# USB_Downstream_Type_C_Port_1.net
KiCad netlist of a schematic drawn in Altium Designer
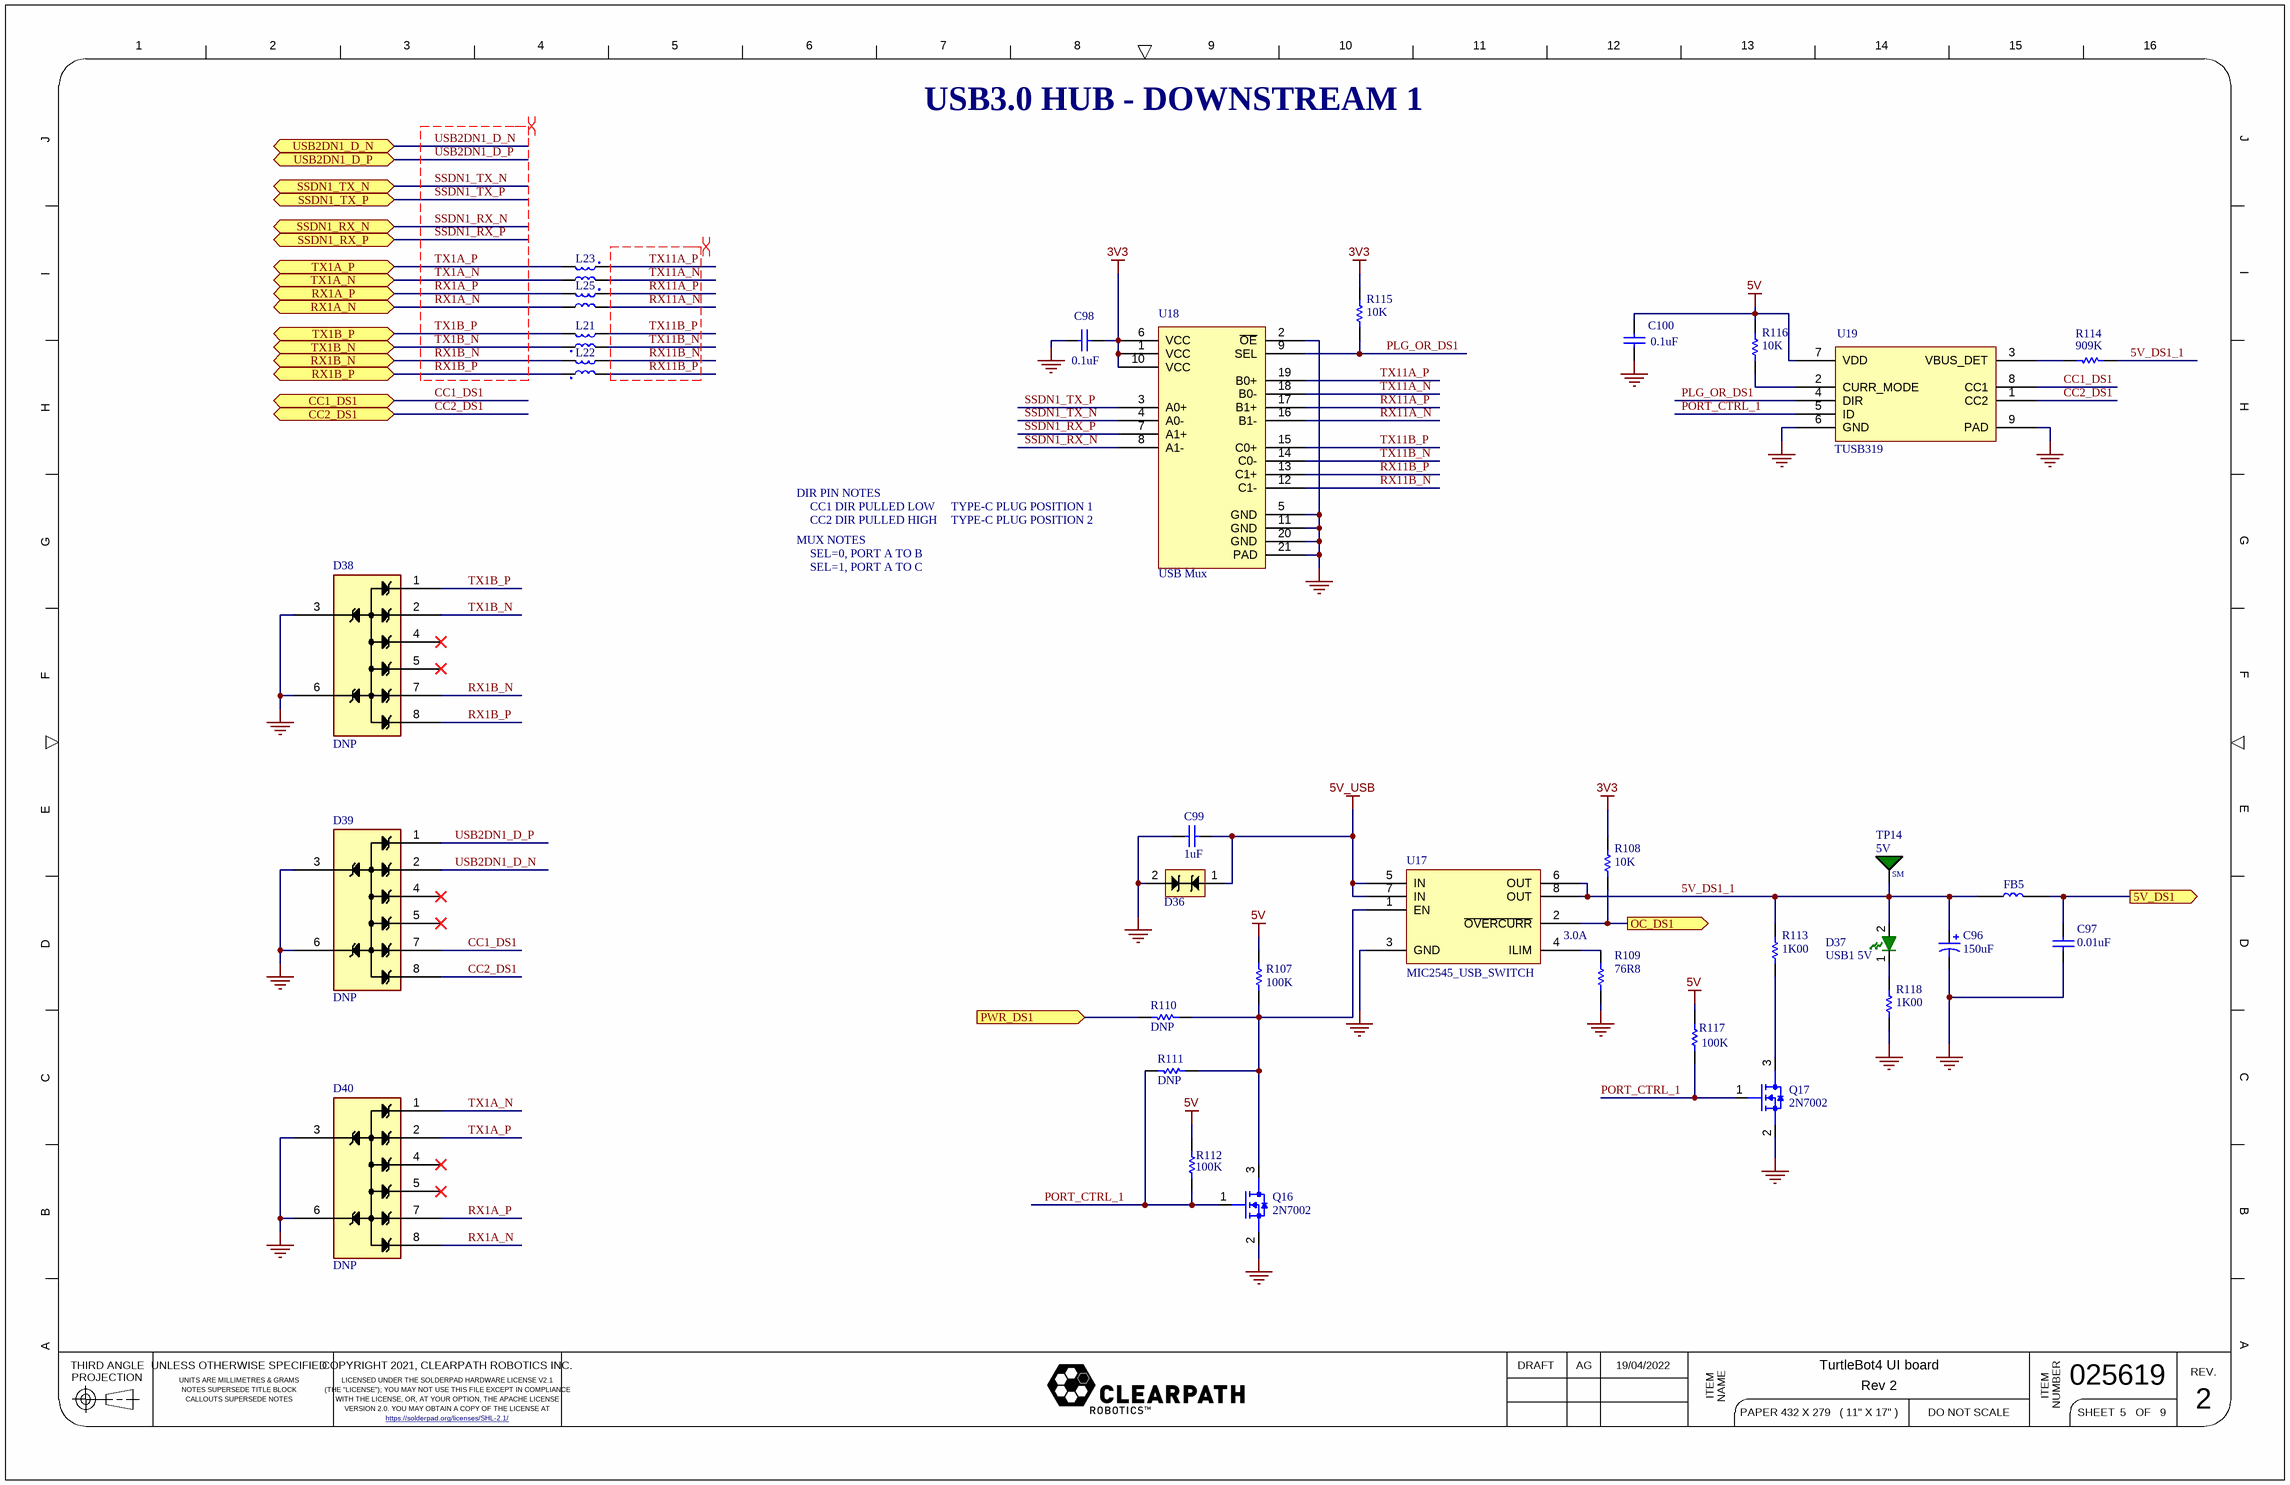
[diagram p0: USB Downstream Type C Port 1.SchDoc]

(export (version "E")
  (design (tool "Eeschema 10.0.6"))
  (components
    (comp (ref "C96")
      (value "150uF")
      (footprint "T494D157K016AT:CAPMP7.6X4.3_3.1N_KEM-M")
      (description "CAP TANT 150UF 10% 16V 2917")
      (fields (field (name "VOLTAGE") "16V") (field (name "TOLERANCE") "10%"))
      (libsource (lib "Miscellaneous Devices") (part "Cap Pol1"))
    )
    (comp (ref "C97")
      (value "0.01uF")
      (footprint "C0805")
      (description "Capacitor")
      (fields (field (name "TOLERANCE") "10%") (field (name "VOLTAGE") "50V"))
      (libsource (lib "CPR_CommonDevices") (part "Capacitor _SMT"))
    )
    (comp (ref "C98")
      (value "0.1uF")
      (footprint "C0805")
      (description "Capacitor")
      (fields (field (name "TOLERANCE") "10%") (field (name "VOLTAGE") "50V"))
      (libsource (lib "CPR_CommonDevices") (part "Capacitor _SMT"))
    )
    (comp (ref "C99")
      (value "1uF")
      (footprint "C0805")
      (description "Capacitor")
      (fields (field (name "TOLERANCE") "-20 +80") (field (name "VOLTAGE") "50V"))
      (libsource (lib "CPR_CommonDevices") (part "Capacitor _SMT"))
    )
    (comp (ref "C100")
      (value "0.1uF")
      (footprint "C0805")
      (description "Capacitor")
      (fields (field (name "TOLERANCE") "10%") (field (name "VOLTAGE") "50V"))
      (libsource (lib "CPR_CommonDevices") (part "Capacitor _SMT"))
    )
    (comp (ref "D36")
      (value "TVS DIODE BIDIR 15V SMC")
      (footprint "General PCB Library:DO-214AA")
      (description "TVS 600W 15V BI-DIR DO-214AA")
      (fields (field (name "MFG") "Littelfuse Inc."))
      (libsource (lib "SMBJ15CA") (part "TVS DIODE BIDIR 15V SMC"))
    )
    (comp (ref "D37")
      (value "USB1 5V")
      (footprint "LED_0805_GRN")
      (description "Green LED")
      (fields (field (name "MFG") "LiteOn"))
      (libsource (lib "Green LED") (part "GREEN_LED"))
    )
    (comp (ref "D38")
      (value "DNP")
      (footprint "ESD7016")
      (description "USB3 TVS diode assy")
      (fields (field (name "MFG") "ON Semi"))
      (libsource (lib "ONSemi_ESD7016") (part "ESD7016"))
    )
    (comp (ref "D39")
      (value "DNP")
      (footprint "ESD7016")
      (description "USB3 TVS diode assy")
      (fields (field (name "MFG") "ON Semi"))
      (libsource (lib "ONSemi_ESD7016") (part "ESD7016"))
    )
    (comp (ref "D40")
      (value "DNP")
      (footprint "ESD7016")
      (description "USB3 TVS diode assy")
      (fields (field (name "MFG") "ON Semi"))
      (libsource (lib "ONSemi_ESD7016") (part "ESD7016"))
    )
    (comp (ref "FB5")
      (value "742792602")
      (footprint "General PCB Library:R0603")
      (description "60 Ohms 1 Signal Line Ferrite Bead 0603 (1608 Metric) 3A 40mOhm")
      (libsource (lib "742792602") (part "742792602"))
    )
    (comp (ref "L21")
      (value "CMC 100MA 2LN 90 OHM SMD2")
      (footprint "cmc_90_ohms:cmc_90_ohms")
      (description "Line Common Mode Choke Surface Mount 90 Ohms 100mA DCR 5Ohm")
      (libsource (lib "cmc_90_ohms") (part "CMC 90_Ohms"))
    )
    (comp (ref "L22")
      (value "CMC 100MA 2LN 90 OHM SMD2")
      (footprint "cmc_90_ohms:cmc_90_ohms")
      (description "Line Common Mode Choke Surface Mount 90 Ohms 100mA DCR 5Ohm")
      (libsource (lib "cmc_90_ohms") (part "CMC 90_Ohms"))
    )
    (comp (ref "L23")
      (value "CMC 100MA 2LN 90 OHM SMD2")
      (footprint "cmc_90_ohms:cmc_90_ohms")
      (description "Line Common Mode Choke Surface Mount 90 Ohms 100mA DCR 5Ohm")
      (libsource (lib "cmc_90_ohms") (part "CMC 90_Ohms"))
    )
    (comp (ref "L25")
      (value "CMC 100MA 2LN 90 OHM SMD2")
      (footprint "cmc_90_ohms:cmc_90_ohms")
      (description "Line Common Mode Choke Surface Mount 90 Ohms 100mA DCR 5Ohm")
      (libsource (lib "cmc_90_ohms") (part "CMC 90_Ohms"))
    )
    (comp (ref "Q16")
      (value "NFET")
      (footprint "SOT-23-3")
      (fields (field (name "MFG PN") "2N7002") (field (name "MFG") "ON Semi"))
      (libsource (lib "NFET_SINGLE") (part "NFET_SNGL"))
    )
    (comp (ref "Q17")
      (value "NFET")
      (footprint "SOT-23-3")
      (fields (field (name "MFG PN") "2N7002") (field (name "MFG") "ON Semi"))
      (libsource (lib "NFET_SINGLE") (part "NFET_SNGL"))
    )
    (comp (ref "R107")
      (value "100K")
      (footprint "R0805")
      (description "Resistor")
      (fields (field (name "TOLERANCE") "1%") (field (name "MFG") "Yageo"))
      (libsource (lib "CPR_CommonDevices") (part "Resistor_SMT"))
    )
    (comp (ref "R108")
      (value "10K")
      (footprint "R0805")
      (description "Resistor")
      (fields (field (name "TOLERANCE") "1%") (field (name "MFG") "Yageo"))
      (libsource (lib "CPR_CommonDevices") (part "Resistor_SMT"))
    )
    (comp (ref "R109")
      (value "3.0A")
      (footprint "R0805")
      (description "Resistor")
      (fields
        (field (name "ALTIUM_VALUE") "76R8")
        (field (name "TOLERANCE") "1%")
        (field (name "MFG") "Yageo")
      )
      (libsource (lib "CPR_CommonDevices") (part "Resistor_SMT"))
    )
    (comp (ref "R110")
      (value "DNP")
      (footprint "R0805")
      (description "Resistor")
      (fields (field (name "MFG") "Yageo") (field (name "Comment") "Resistor_SMT"))
      (libsource (lib "") (part "Resistor_SMT_1"))
    )
    (comp (ref "R111")
      (value "DNP")
      (footprint "R0805")
      (description "Resistor")
      (fields (field (name "MFG") "Yageo") (field (name "Comment") "Resistor_SMT"))
      (libsource (lib "") (part "Resistor_SMT_1"))
    )
    (comp (ref "R112")
      (value "100K")
      (footprint "R0805")
      (description "Resistor")
      (fields (field (name "TOLERANCE") "1%") (field (name "MFG") "Yageo"))
      (libsource (lib "CPR_CommonDevices") (part "Resistor_SMT"))
    )
    (comp (ref "R113")
      (value "1K00")
      (footprint "R0805")
      (description "Resistor")
      (fields (field (name "TOLERANCE") "1%") (field (name "MFG") "Yageo"))
      (libsource (lib "CPR_CommonDevices") (part "Resistor_SMT"))
    )
    (comp (ref "R114")
      (value "909K")
      (footprint "R0805")
      (description "Resistor")
      (fields (field (name "TOLERANCE") "1%") (field (name "MFG") "Yageo"))
      (libsource (lib "CPR_CommonDevices") (part "Resistor_SMT"))
    )
    (comp (ref "R115")
      (value "10K")
      (footprint "R0805")
      (description "Resistor")
      (fields (field (name "TOLERANCE") "1%") (field (name "MFG") "Yageo"))
      (libsource (lib "CPR_CommonDevices") (part "Resistor_SMT"))
    )
    (comp (ref "R116")
      (value "10K")
      (footprint "R0805")
      (description "Resistor")
      (fields (field (name "TOLERANCE") "1%") (field (name "MFG") "Yageo"))
      (libsource (lib "CPR_CommonDevices") (part "Resistor_SMT"))
    )
    (comp (ref "R117")
      (value "100K")
      (footprint "R0805")
      (description "Resistor")
      (fields (field (name "TOLERANCE") "1%") (field (name "MFG") "Yageo"))
      (libsource (lib "CPR_CommonDevices") (part "Resistor_SMT"))
    )
    (comp (ref "R118")
      (value "1K00")
      (footprint "R0805")
      (description "Resistor")
      (fields (field (name "TOLERANCE") "1%") (field (name "MFG") "Yageo"))
      (libsource (lib "CPR_CommonDevices") (part "Resistor_SMT"))
    )
    (comp (ref "TP14")
      (value "5V")
      (footprint "TP_28SM")
      (description "Test point, 28 Mil exposed pad")
      (fields (field (name "MANUFACTURER") "Clearpath Robotics Inc."))
      (libsource (lib "Test Points") (part "TP_28SM"))
    )
    (comp (ref "U17")
      (value "MIC2545_USB_SWITCH")
      (footprint "SOIC-8-150")
      (description "IC PWR SWITCH N-CHAN 1:1 8SOIC")
      (fields (field (name "MFG") "Microchip"))
      (libsource (lib "MIC2545") (part "MIC2545_USB_SWITCH"))
    )
    (comp (ref "U18")
      (value "USB Mux")
      (footprint "TQFN20")
      (description "TC7PCI3212MT,LF USB3.0 Mux")
      (fields (field (name "MANUFACTURER") "Toshiba"))
      (libsource (lib "TOSHIBA TC7PCI3212MT") (part "TC7PCI3212"))
    )
    (comp (ref "U19")
      (value "TUSB319")
      (footprint "WSON8")
      (description "USB Type C Controller")
      (fields (field (name "MFG") "Texas Instruments"))
      (libsource (lib "TUSB319") (part "TUSB319"))
    )
  )
  (nets
    (net (code "1") (name "/5V_DS1") (class "Default")
      (node (ref "C97") (pin "1") (pinfunction "1_1") (pintype "passive"))
      (node (ref "FB5") (pin "2") (pinfunction "2_2") (pintype "passive"))
    )
    (net (code "2") (name "/5V_DS1_1") (class "Default")
      (node (ref "C96") (pin "1") (pinfunction "1_1") (pintype "passive"))
      (node (ref "D37") (pin "2") (pinfunction "RA_2") (pintype "passive"))
      (node (ref "FB5") (pin "1") (pinfunction "1_1") (pintype "passive"))
      (node (ref "R113") (pin "1") (pinfunction "1_1") (pintype "passive"))
      (node (ref "R114") (pin "2") (pinfunction "2_2") (pintype "passive"))
      (node (ref "TP14") (pin "1") (pintype "passive"))
      (node (ref "U17") (pin "6") (pinfunction "OUT_6") (pintype "passive"))
      (node (ref "U17") (pin "8") (pinfunction "OUT_8") (pintype "passive"))
    )
    (net (code "3") (name "/CC1_DS1") (class "Default")
      (node (ref "D39") (pin "7") (pintype "passive"))
      (node (ref "U19") (pin "8") (pinfunction "CC1_8") (pintype "passive"))
    )
    (net (code "4") (name "/CC2_DS1") (class "Default")
      (node (ref "D39") (pin "8") (pintype "passive"))
      (node (ref "U19") (pin "1") (pinfunction "CC2_1") (pintype "passive"))
    )
    (net (code "5") (name "/OC_DS1") (class "Default")
      (node (ref "R108") (pin "2") (pinfunction "2_2") (pintype "passive"))
      (node (ref "U17") (pin "2") (pinfunction "~{OVERCURR}_2") (pintype "passive"))
    )
    (net (code "6") (name "/PLG_OR_DS1") (class "Default")
      (node (ref "R115") (pin "2") (pinfunction "2_2") (pintype "passive"))
      (node (ref "U18") (pin "9") (pinfunction "SEL_9") (pintype "passive"))
      (node (ref "U19") (pin "4") (pinfunction "DIR_4") (pintype "passive"))
    )
    (net (code "7") (name "/PORT_CTRL_1") (class "Default")
      (node (ref "Q16") (pin "1") (pinfunction "G1_1") (pintype "passive"))
      (node (ref "Q17") (pin "1") (pinfunction "G1_1") (pintype "passive"))
      (node (ref "R111") (pin "1") (pinfunction "1_1") (pintype "passive"))
      (node (ref "R112") (pin "1") (pinfunction "1_1") (pintype "passive"))
      (node (ref "R117") (pin "1") (pinfunction "1_1") (pintype "passive"))
      (node (ref "U19") (pin "5") (pinfunction "ID_5") (pintype "passive"))
    )
    (net (code "8") (name "/PWR_DS1") (class "Default")
      (node (ref "R110") (pin "1") (pinfunction "1_1") (pintype "passive"))
    )
    (net (code "9") (name "/RX1A_N") (class "Default")
      (node (ref "D40") (pin "8") (pintype "passive"))
      (node (ref "L25") (pin "3") (pinfunction "3_3") (pintype "passive"))
    )
    (net (code "10") (name "/RX1A_P") (class "Default")
      (node (ref "D40") (pin "7") (pintype "passive"))
      (node (ref "L25") (pin "4") (pinfunction "4_4") (pintype "passive"))
    )
    (net (code "11") (name "/RX1B_N") (class "Default")
      (node (ref "D38") (pin "7") (pintype "passive"))
      (node (ref "L22") (pin "2") (pinfunction "2_2") (pintype "passive"))
    )
    (net (code "12") (name "/RX1B_P") (class "Default")
      (node (ref "D38") (pin "8") (pintype "passive"))
      (node (ref "L22") (pin "1") (pinfunction "1_1") (pintype "passive"))
    )
    (net (code "13") (name "/RX11A_N") (class "Default")
      (node (ref "L25") (pin "2") (pinfunction "2_2") (pintype "passive"))
      (node (ref "U18") (pin "16") (pinfunction "B1-_16") (pintype "passive"))
    )
    (net (code "14") (name "/RX11A_P") (class "Default")
      (node (ref "L25") (pin "1") (pinfunction "1_1") (pintype "passive"))
      (node (ref "U18") (pin "17") (pinfunction "B1+_17") (pintype "passive"))
    )
    (net (code "15") (name "/RX11B_N") (class "Default")
      (node (ref "L22") (pin "3") (pinfunction "3_3") (pintype "passive"))
      (node (ref "U18") (pin "12") (pinfunction "C1-_12") (pintype "passive"))
    )
    (net (code "16") (name "/RX11B_P") (class "Default")
      (node (ref "L22") (pin "4") (pinfunction "4_4") (pintype "passive"))
      (node (ref "U18") (pin "13") (pinfunction "C1+_13") (pintype "passive"))
    )
    (net (code "17") (name "/SSDN1_RX_N") (class "Default")
      (node (ref "U18") (pin "8") (pinfunction "A1-_8") (pintype "passive"))
    )
    (net (code "18") (name "/SSDN1_RX_P") (class "Default")
      (node (ref "U18") (pin "7") (pinfunction "A1+_7") (pintype "passive"))
    )
    (net (code "19") (name "/SSDN1_TX_N") (class "Default")
      (node (ref "U18") (pin "4") (pinfunction "A0-_4") (pintype "passive"))
    )
    (net (code "20") (name "/SSDN1_TX_P") (class "Default")
      (node (ref "U18") (pin "3") (pinfunction "A0+_3") (pintype "passive"))
    )
    (net (code "21") (name "/TX1A_N") (class "Default")
      (node (ref "D40") (pin "1") (pinfunction "1_1") (pintype "passive"))
      (node (ref "L23") (pin "3") (pinfunction "3_3") (pintype "passive"))
    )
    (net (code "22") (name "/TX1A_P") (class "Default")
      (node (ref "D40") (pin "2") (pintype "passive"))
      (node (ref "L23") (pin "4") (pinfunction "4_4") (pintype "passive"))
    )
    (net (code "23") (name "/TX1B_N") (class "Default")
      (node (ref "D38") (pin "2") (pintype "passive"))
      (node (ref "L21") (pin "1") (pinfunction "1_1") (pintype "passive"))
    )
    (net (code "24") (name "/TX1B_P") (class "Default")
      (node (ref "D38") (pin "1") (pinfunction "1_1") (pintype "passive"))
      (node (ref "L21") (pin "2") (pinfunction "2_2") (pintype "passive"))
    )
    (net (code "25") (name "/TX11A_N") (class "Default")
      (node (ref "L23") (pin "2") (pinfunction "2_2") (pintype "passive"))
      (node (ref "U18") (pin "18") (pinfunction "B0-_18") (pintype "passive"))
    )
    (net (code "26") (name "/TX11A_P") (class "Default")
      (node (ref "L23") (pin "1") (pinfunction "1_1") (pintype "passive"))
      (node (ref "U18") (pin "19") (pinfunction "B0+_19") (pintype "passive"))
    )
    (net (code "27") (name "/TX11B_N") (class "Default")
      (node (ref "L21") (pin "4") (pinfunction "4_4") (pintype "passive"))
      (node (ref "U18") (pin "14") (pinfunction "C0-_14") (pintype "passive"))
    )
    (net (code "28") (name "/TX11B_P") (class "Default")
      (node (ref "L21") (pin "3") (pinfunction "3_3") (pintype "passive"))
      (node (ref "U18") (pin "15") (pinfunction "C0+_15") (pintype "passive"))
    )
    (net (code "29") (name "/USB2DN1_D_N") (class "Default") (node (ref "D39") (pin "2") (pintype "passive")))
    (net (code "30") (name "/USB2DN1_D_P") (class "Default")
      (node (ref "D39") (pin "1") (pinfunction "1_1") (pintype "passive"))
    )
    (net (code "31") (name "3V3") (class "Default")
      (node (ref "C98") (pin "1") (pinfunction "1_1") (pintype "passive"))
      (node (ref "R108") (pin "1") (pinfunction "1_1") (pintype "passive"))
      (node (ref "R115") (pin "1") (pinfunction "1_1") (pintype "passive"))
      (node (ref "U18") (pin "1") (pinfunction "VCC_1") (pintype "passive"))
      (node (ref "U18") (pin "10") (pinfunction "VCC_10") (pintype "passive"))
      (node (ref "U18") (pin "6") (pinfunction "VCC_6") (pintype "passive"))
    )
    (net (code "32") (name "5V") (class "Default")
      (node (ref "C100") (pin "1") (pinfunction "1_1") (pintype "passive"))
      (node (ref "R107") (pin "2") (pinfunction "2_2") (pintype "passive"))
      (node (ref "R112") (pin "2") (pinfunction "2_2") (pintype "passive"))
      (node (ref "R116") (pin "1") (pinfunction "1_1") (pintype "passive"))
      (node (ref "R117") (pin "2") (pinfunction "2_2") (pintype "passive"))
      (node (ref "U19") (pin "7") (pinfunction "VDD_7") (pintype "passive"))
    )
    (net (code "33") (name "5V_USB") (class "Default")
      (node (ref "C99") (pin "2") (pinfunction "2_2") (pintype "passive"))
      (node (ref "D36") (pin "1") (pintype "passive"))
      (node (ref "U17") (pin "5") (pinfunction "IN_5") (pintype "passive"))
      (node (ref "U17") (pin "7") (pinfunction "IN_7") (pintype "passive"))
    )
    (net (code "34") (name "GND") (class "Default")
      (node (ref "C100") (pin "2") (pinfunction "2_2") (pintype "passive"))
      (node (ref "C96") (pin "2") (pinfunction "2_2") (pintype "passive"))
      (node (ref "C97") (pin "2") (pinfunction "2_2") (pintype "passive"))
      (node (ref "C98") (pin "2") (pinfunction "2_2") (pintype "passive"))
      (node (ref "C99") (pin "1") (pinfunction "1_1") (pintype "passive"))
      (node (ref "D36") (pin "2") (pintype "passive"))
      (node (ref "D38") (pin "3") (pintype "passive"))
      (node (ref "D38") (pin "6") (pintype "passive"))
      (node (ref "D39") (pin "3") (pintype "passive"))
      (node (ref "D39") (pin "6") (pintype "passive"))
      (node (ref "D40") (pin "3") (pintype "passive"))
      (node (ref "D40") (pin "6") (pintype "passive"))
      (node (ref "Q16") (pin "2") (pinfunction "D1_2") (pintype "passive"))
      (node (ref "Q17") (pin "2") (pinfunction "D1_2") (pintype "passive"))
      (node (ref "R109") (pin "1") (pinfunction "1_1") (pintype "passive"))
      (node (ref "R118") (pin "2") (pinfunction "2_2") (pintype "passive"))
      (node (ref "U17") (pin "3") (pinfunction "GND_3") (pintype "passive"))
      (node (ref "U18") (pin "11") (pinfunction "GND_11") (pintype "passive"))
      (node (ref "U18") (pin "2") (pinfunction "~{OE}_2") (pintype "passive"))
      (node (ref "U18") (pin "20") (pinfunction "GND_20") (pintype "passive"))
      (node (ref "U18") (pin "21") (pinfunction "PAD_21") (pintype "passive"))
      (node (ref "U18") (pin "5") (pinfunction "GND_5") (pintype "passive"))
      (node (ref "U19") (pin "6") (pinfunction "GND_6") (pintype "passive"))
      (node (ref "U19") (pin "9") (pinfunction "PAD_9") (pintype "passive"))
    )
    (net (code "35") (name "Net-(D37-RK)") (class "Default")
      (node (ref "D37") (pin "1") (pinfunction "RK_1") (pintype "passive"))
      (node (ref "R118") (pin "1") (pinfunction "1_1") (pintype "passive"))
    )
    (net (code "36") (name "Net-(Q16-S1)") (class "Default")
      (node (ref "Q16") (pin "3") (pinfunction "S1_3") (pintype "passive"))
      (node (ref "R107") (pin "1") (pinfunction "1_1") (pintype "passive"))
      (node (ref "R110") (pin "2") (pinfunction "2_2") (pintype "passive"))
      (node (ref "R111") (pin "2") (pinfunction "2_2") (pintype "passive"))
      (node (ref "U17") (pin "1") (pinfunction "EN_1") (pintype "passive"))
    )
    (net (code "37") (name "Net-(Q17-S1)") (class "Default")
      (node (ref "Q17") (pin "3") (pinfunction "S1_3") (pintype "passive"))
      (node (ref "R113") (pin "2") (pinfunction "2_2") (pintype "passive"))
    )
    (net (code "38") (name "Net-(U17-ILIM)") (class "Default")
      (node (ref "R109") (pin "2") (pinfunction "2_2") (pintype "passive"))
      (node (ref "U17") (pin "4") (pinfunction "ILIM_4") (pintype "passive"))
    )
    (net (code "39") (name "Net-(U19-CURR_MODE)") (class "Default")
      (node (ref "R116") (pin "2") (pinfunction "2_2") (pintype "passive"))
      (node (ref "U19") (pin "2") (pinfunction "CURR_MODE_2") (pintype "passive"))
    )
    (net (code "40") (name "Net-(U19-VBUS_DET)") (class "Default")
      (node (ref "R114") (pin "1") (pinfunction "1_1") (pintype "passive"))
      (node (ref "U19") (pin "3") (pinfunction "VBUS_DET_3") (pintype "passive"))
    )
    (net (code "41") (name "unconnected-(D38-Pad4)") (class "Default")
      (node (ref "D38") (pin "4") (pintype "passive+no_connect"))
    )
    (net (code "42") (name "unconnected-(D38-Pad5)") (class "Default")
      (node (ref "D38") (pin "5") (pintype "passive+no_connect"))
    )
    (net (code "43") (name "unconnected-(D39-Pad4)") (class "Default")
      (node (ref "D39") (pin "4") (pintype "passive+no_connect"))
    )
    (net (code "44") (name "unconnected-(D39-Pad5)") (class "Default")
      (node (ref "D39") (pin "5") (pintype "passive+no_connect"))
    )
    (net (code "45") (name "unconnected-(D40-Pad4)") (class "Default")
      (node (ref "D40") (pin "4") (pintype "passive+no_connect"))
    )
    (net (code "46") (name "unconnected-(D40-Pad5)") (class "Default")
      (node (ref "D40") (pin "5") (pintype "passive+no_connect"))
    )
  )
)
